# STM32F429ZI.net
KiCad netlist of a schematic drawn in Altium Designer
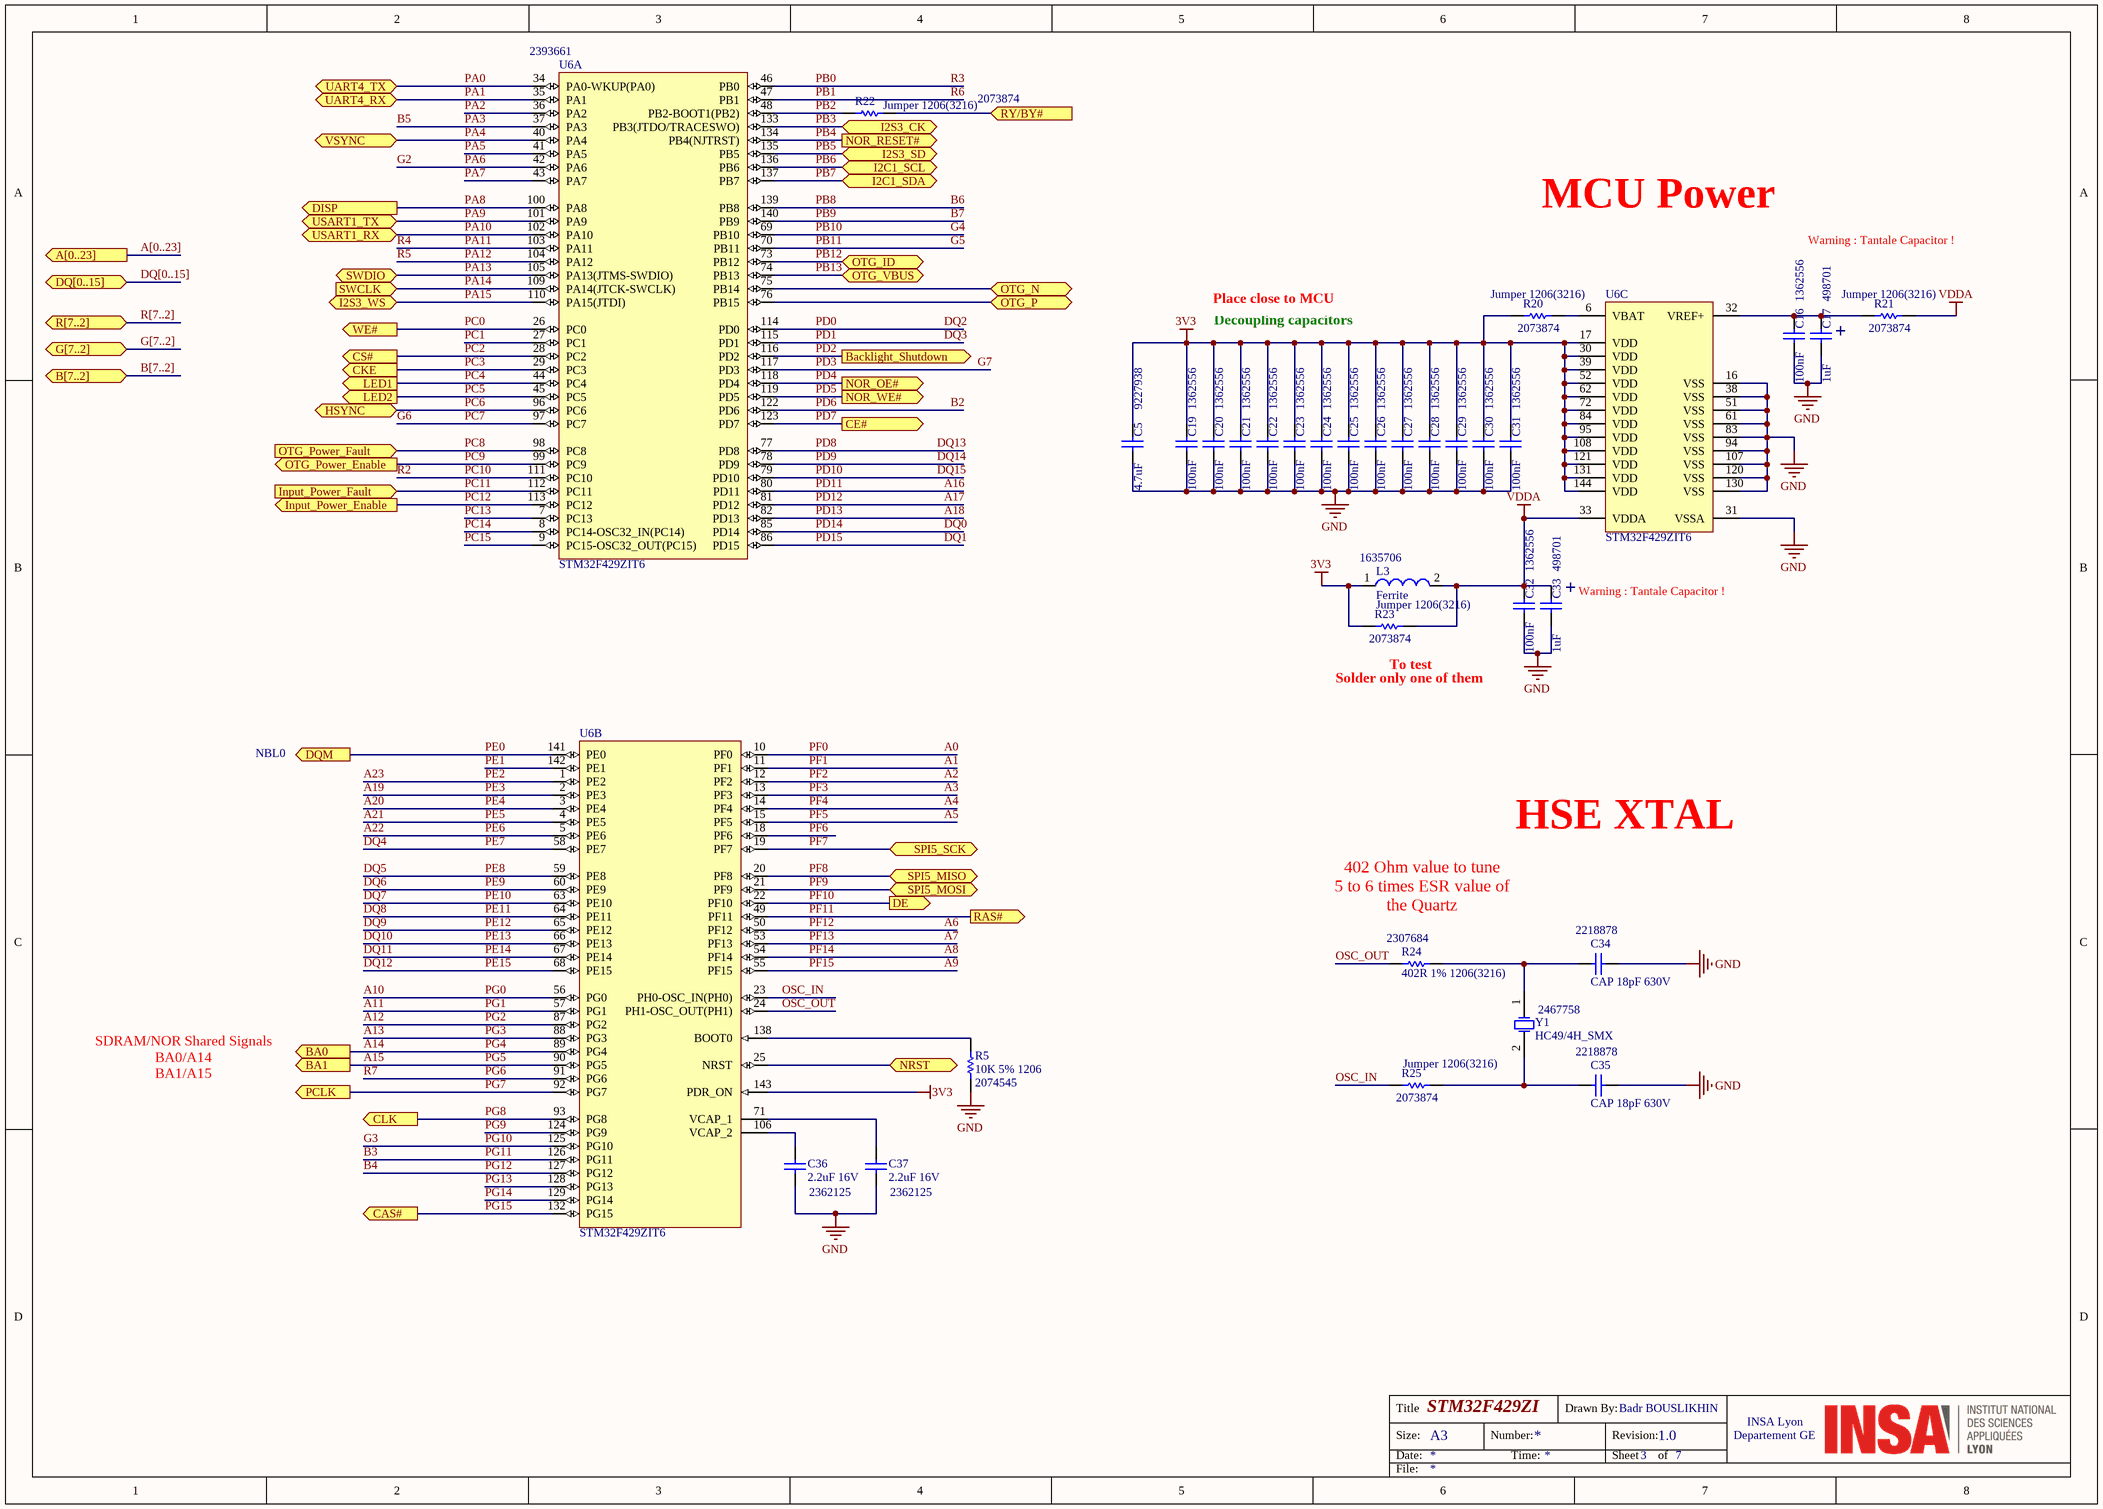
[diagram p0: STM32F429ZI.SchDoc]

(export (version "E")
  (design (tool "Eeschema 10.0.6"))
  (components
    (comp (ref "C5")
      (value "4.7uF")
      (footprint "CAPC1206(3216)190_N")
      (description "CAP 4.7uF 50V ±10% 1206 (3216 Metric) Thickness 1.9mm SMD")
      (fields (field (name "TOLERANCE") "±10%") (field (name "SUPPLIER PART NUMBER 1") "9227938"))
      (libsource (lib "Altium Content Vault") (part "CAP"))
    )
    (comp (ref "C16")
      (value "100nF")
      (footprint "CAPC0603(1608)100_N")
      (description "CAP 100nF 50V ±10% 0603 (1608 Metric) Thickness 1mm SMD")
      (fields (field (name "TOLERANCE") "±10%") (field (name "SUPPLIER PART NUMBER 1") "1362556"))
      (libsource (lib "Altium Content Vault") (part "CMP-1035-02592-1"))
    )
    (comp (ref "C17")
      (value "1uF")
      (footprint "CAPC1206(3216)170_L")
      (description "CAP 1uF 16V ±10% 1206 (3216 Metric) Thickness 1.7mm SMD")
      (fields (field (name "TOLERANCE") "±10%") (field (name "SUPPLIER PART NUMBER 1") "498701"))
      (libsource (lib "Altium Content Vault") (part "CAP"))
    )
    (comp (ref "C19")
      (value "100nF")
      (footprint "CAPC0603(1608)100_N")
      (description "CAP 100nF 50V ±10% 0603 (1608 Metric) Thickness 1mm SMD")
      (fields (field (name "TOLERANCE") "±10%") (field (name "SUPPLIER PART NUMBER 1") "1362556"))
      (libsource (lib "Altium Content Vault") (part "CMP-1035-02592-1"))
    )
    (comp (ref "C20")
      (value "100nF")
      (footprint "CAPC0603(1608)100_N")
      (description "CAP 100nF 50V ±10% 0603 (1608 Metric) Thickness 1mm SMD")
      (fields (field (name "TOLERANCE") "±10%") (field (name "SUPPLIER PART NUMBER 1") "1362556"))
      (libsource (lib "Altium Content Vault") (part "CMP-1035-02592-1"))
    )
    (comp (ref "C21")
      (value "100nF")
      (footprint "CAPC0603(1608)100_N")
      (description "CAP 100nF 50V ±10% 0603 (1608 Metric) Thickness 1mm SMD")
      (fields (field (name "TOLERANCE") "±10%") (field (name "SUPPLIER PART NUMBER 1") "1362556"))
      (libsource (lib "Altium Content Vault") (part "CMP-1035-02592-1"))
    )
    (comp (ref "C22")
      (value "100nF")
      (footprint "CAPC0603(1608)100_N")
      (description "CAP 100nF 50V ±10% 0603 (1608 Metric) Thickness 1mm SMD")
      (fields (field (name "TOLERANCE") "±10%") (field (name "SUPPLIER PART NUMBER 1") "1362556"))
      (libsource (lib "Altium Content Vault") (part "CMP-1035-02592-1"))
    )
    (comp (ref "C23")
      (value "100nF")
      (footprint "CAPC0603(1608)100_N")
      (description "CAP 100nF 50V ±10% 0603 (1608 Metric) Thickness 1mm SMD")
      (fields (field (name "TOLERANCE") "±10%") (field (name "SUPPLIER PART NUMBER 1") "1362556"))
      (libsource (lib "Altium Content Vault") (part "CMP-1035-02592-1"))
    )
    (comp (ref "C24")
      (value "100nF")
      (footprint "CAPC0603(1608)100_N")
      (description "CAP 100nF 50V ±10% 0603 (1608 Metric) Thickness 1mm SMD")
      (fields (field (name "TOLERANCE") "±10%") (field (name "SUPPLIER PART NUMBER 1") "1362556"))
      (libsource (lib "Altium Content Vault") (part "CMP-1035-02592-1"))
    )
    (comp (ref "C25")
      (value "100nF")
      (footprint "CAPC0603(1608)100_N")
      (description "CAP 100nF 50V ±10% 0603 (1608 Metric) Thickness 1mm SMD")
      (fields (field (name "TOLERANCE") "±10%") (field (name "SUPPLIER PART NUMBER 1") "1362556"))
      (libsource (lib "Altium Content Vault") (part "CMP-1035-02592-1"))
    )
    (comp (ref "C26")
      (value "100nF")
      (footprint "CAPC0603(1608)100_N")
      (description "CAP 100nF 50V ±10% 0603 (1608 Metric) Thickness 1mm SMD")
      (fields (field (name "TOLERANCE") "±10%") (field (name "SUPPLIER PART NUMBER 1") "1362556"))
      (libsource (lib "Altium Content Vault") (part "CMP-1035-02592-1"))
    )
    (comp (ref "C27")
      (value "100nF")
      (footprint "CAPC0603(1608)100_N")
      (description "CAP 100nF 50V ±10% 0603 (1608 Metric) Thickness 1mm SMD")
      (fields (field (name "TOLERANCE") "±10%") (field (name "SUPPLIER PART NUMBER 1") "1362556"))
      (libsource (lib "Altium Content Vault") (part "CMP-1035-02592-1"))
    )
    (comp (ref "C28")
      (value "100nF")
      (footprint "CAPC0603(1608)100_N")
      (description "CAP 100nF 50V ±10% 0603 (1608 Metric) Thickness 1mm SMD")
      (fields (field (name "TOLERANCE") "±10%") (field (name "SUPPLIER PART NUMBER 1") "1362556"))
      (libsource (lib "Altium Content Vault") (part "CMP-1035-02592-1"))
    )
    (comp (ref "C29")
      (value "100nF")
      (footprint "CAPC0603(1608)100_N")
      (description "CAP 100nF 50V ±10% 0603 (1608 Metric) Thickness 1mm SMD")
      (fields (field (name "TOLERANCE") "±10%") (field (name "SUPPLIER PART NUMBER 1") "1362556"))
      (libsource (lib "Altium Content Vault") (part "CMP-1035-02592-1"))
    )
    (comp (ref "C30")
      (value "100nF")
      (footprint "CAPC0603(1608)100_N")
      (description "CAP 100nF 50V ±10% 0603 (1608 Metric) Thickness 1mm SMD")
      (fields (field (name "TOLERANCE") "±10%") (field (name "SUPPLIER PART NUMBER 1") "1362556"))
      (libsource (lib "Altium Content Vault") (part "CMP-1035-02592-1"))
    )
    (comp (ref "C31")
      (value "100nF")
      (footprint "CAPC0603(1608)100_N")
      (description "CAP 100nF 50V ±10% 0603 (1608 Metric) Thickness 1mm SMD")
      (fields (field (name "TOLERANCE") "±10%") (field (name "SUPPLIER PART NUMBER 1") "1362556"))
      (libsource (lib "Altium Content Vault") (part "CMP-1035-02592-1"))
    )
    (comp (ref "C32")
      (value "100nF")
      (footprint "CAPC0603(1608)100_N")
      (description "CAP 100nF 50V ±10% 0603 (1608 Metric) Thickness 1mm SMD")
      (fields (field (name "TOLERANCE") "±10%") (field (name "SUPPLIER PART NUMBER 1") "1362556"))
      (libsource (lib "Altium Content Vault") (part "CMP-1035-02592-1"))
    )
    (comp (ref "C33")
      (value "1uF")
      (footprint "CAPC1206(3216)170_L")
      (description "CAP 1uF 16V ±10% 1206 (3216 Metric) Thickness 1.7mm SMD")
      (fields (field (name "TOLERANCE") "±10%") (field (name "SUPPLIER PART NUMBER 1") "498701"))
      (libsource (lib "Altium Content Vault") (part "CAP"))
    )
    (comp (ref "C34")
      (value "CAP 18pF 630V")
      (footprint "CAPC1206(3216)170_L")
      (description "CAP 18pF 500V ±5% 1206 (3216 Metric) Thickness 1.7mm SMD")
      (fields (field (name "TOLERANCE") "±5%") (field (name "SUPPLIER PART NUMBER 1") "2218878"))
      (libsource (lib "Altium Content Vault") (part "CMP-1037-00919-1"))
    )
    (comp (ref "C35")
      (value "CAP 18pF 630V")
      (footprint "CAPC1206(3216)170_L")
      (description "CAP 18pF 500V ±5% 1206 (3216 Metric) Thickness 1.7mm SMD")
      (fields (field (name "TOLERANCE") "±5%") (field (name "SUPPLIER PART NUMBER 1") "2218878"))
      (libsource (lib "Altium Content Vault") (part "CMP-1037-00919-1"))
    )
    (comp (ref "C36")
      (value "2.2uF 16V")
      (footprint "CAPC1206(3216)190_L")
      (description "CAP 2.2uF 16V ±20% 1206 (3216 Metric) Thickness 1.9mm SMD")
      (fields (field (name "TOLERANCE") "±20%") (field (name "SUPPLIER PART NUMBER 1") "2362125"))
      (libsource (lib "Altium Content Vault") (part "CMP-1037-04816-1"))
    )
    (comp (ref "C37")
      (value "2.2uF 16V")
      (footprint "CAPC1206(3216)190_L")
      (description "CAP 2.2uF 16V ±20% 1206 (3216 Metric) Thickness 1.9mm SMD")
      (fields (field (name "TOLERANCE") "±20%") (field (name "SUPPLIER PART NUMBER 1") "2362125"))
      (libsource (lib "Altium Content Vault") (part "CMP-1037-04816-1"))
    )
    (comp (ref "L3")
      (value "Ferrite")
      (footprint "SMD-0603")
      (description "SMD EMI Suppression Ferrite Bead WE-CBF, Z = 600 Ohm")
      (fields (field (name "SUPPLIER PART NUMBER 1") "1635706"))
      (libsource (lib "Altium Content Vault") (part "CMP-0220-00181-1"))
    )
    (comp (ref "R5")
      (value "10K 5% 1206")
      (footprint "RESC1206(3216)_M")
      (description "10K 0.25W 5% 1206 (3216 Metric)  SMD")
      (fields
        (field (name "POWER") "0.25 W")
        (field (name "TOLERANCE") "5 %")
        (field (name "SUPPLIER PART NUMBER 1") "2074545")
      )
      (libsource (lib "Altium Content Vault") (part "CMP-1014-00098-1"))
    )
    (comp (ref "R20")
      (value "Jumper 1206(3216)")
      (footprint "RESC1206(3216)_L")
      (description "Jumper 1206 (3216 Metric)")
      (fields (field (name "TOLERANCE") "None") (field (name "SUPPLIER PART NUMBER 1") "2073874"))
      (libsource (lib "Altium Content Vault") (part "RES"))
    )
    (comp (ref "R21")
      (value "Jumper 1206(3216)")
      (footprint "RESC1206(3216)_L")
      (description "Jumper 1206 (3216 Metric)")
      (fields (field (name "TOLERANCE") "None") (field (name "SUPPLIER PART NUMBER 1") "2073874"))
      (libsource (lib "Altium Content Vault") (part "RES"))
    )
    (comp (ref "R22")
      (value "Jumper 1206(3216)")
      (footprint "RESC1206(3216)_L")
      (description "Jumper 1206 (3216 Metric)")
      (fields (field (name "TOLERANCE") "None") (field (name "SUPPLIER PART NUMBER 1") "2073874"))
      (libsource (lib "Altium Content Vault") (part "RES"))
    )
    (comp (ref "R23")
      (value "Jumper 1206(3216)")
      (footprint "RESC1206(3216)_L")
      (description "Jumper 1206 (3216 Metric)")
      (fields (field (name "TOLERANCE") "None") (field (name "SUPPLIER PART NUMBER 1") "2073874"))
      (libsource (lib "Altium Content Vault") (part "RES"))
    )
    (comp (ref "R24")
      (value "402R 1% 1206(3216)")
      (footprint "RESC1206(3216)_L")
      (description "402R 0.25W 1% 1206 (3216 Metric)  SMD")
      (fields
        (field (name "POWER") "0.25 W")
        (field (name "TOLERANCE") "1 %")
        (field (name "SUPPLIER PART NUMBER 1") "2307684")
      )
      (libsource (lib "Altium Content Vault") (part "RES"))
    )
    (comp (ref "R25")
      (value "Jumper 1206(3216)")
      (footprint "RESC1206(3216)_L")
      (description "Jumper 1206 (3216 Metric)")
      (fields (field (name "TOLERANCE") "None") (field (name "SUPPLIER PART NUMBER 1") "2073874"))
      (libsource (lib "Altium Content Vault") (part "RES"))
    )
    (comp (ref "U6")
      (value "STM32F429ZIT6")
      (footprint "STM-LQFP144_L")
      (fields
        (field (name "MANUFACTURER") "STMicroelectronics")
        (field (name "SUPPLIER PART NUMBER 1") "2393661")
      )
      (libsource (lib "Altium Content Vault") (part "MC-ARM-STM32F4X9-SQ144"))
    )
    (comp (ref "Y1")
      (value "HC49/4H_SMX")
      (footprint "HC49/4H_SMX")
      (description "Surface Mount Quartz Crystal")
      (fields (field (name "SUPPLIER PART NUMBER 1") "2467758") (field (name "PUBLISHER") "Altium Limited"))
      (libsource (lib "C-MAC Crystal Oscillator") (part "HC49/4H_SMX"))
    )
  )
  (nets
    (net (code "1") (name "/A0") (class "Default")
      (node (ref "U6") (pin "10") (pinfunction "PF0_10") (pintype "bidirectional"))
    )
    (net (code "2") (name "/A1") (class "Default")
      (node (ref "U6") (pin "11") (pinfunction "PF1_11") (pintype "bidirectional"))
    )
    (net (code "3") (name "/A2") (class "Default")
      (node (ref "U6") (pin "12") (pinfunction "PF2_12") (pintype "bidirectional"))
    )
    (net (code "4") (name "/A3") (class "Default")
      (node (ref "U6") (pin "13") (pinfunction "PF3_13") (pintype "bidirectional"))
    )
    (net (code "5") (name "/A4") (class "Default")
      (node (ref "U6") (pin "14") (pinfunction "PF4_14") (pintype "bidirectional"))
    )
    (net (code "6") (name "/A5") (class "Default")
      (node (ref "U6") (pin "15") (pinfunction "PF5_15") (pintype "bidirectional"))
    )
    (net (code "7") (name "/A6") (class "Default")
      (node (ref "U6") (pin "50") (pinfunction "PF12_50") (pintype "bidirectional"))
    )
    (net (code "8") (name "/A7") (class "Default")
      (node (ref "U6") (pin "53") (pinfunction "PF13_53") (pintype "bidirectional"))
    )
    (net (code "9") (name "/A8") (class "Default")
      (node (ref "U6") (pin "54") (pinfunction "PF14_54") (pintype "bidirectional"))
    )
    (net (code "10") (name "/A9") (class "Default")
      (node (ref "U6") (pin "55") (pinfunction "PF15_55") (pintype "bidirectional"))
    )
    (net (code "11") (name "/A10") (class "Default")
      (node (ref "U6") (pin "56") (pinfunction "PG0_56") (pintype "bidirectional"))
    )
    (net (code "12") (name "/A11") (class "Default")
      (node (ref "U6") (pin "57") (pinfunction "PG1_57") (pintype "bidirectional"))
    )
    (net (code "13") (name "/A12") (class "Default")
      (node (ref "U6") (pin "87") (pinfunction "PG2_87") (pintype "bidirectional"))
    )
    (net (code "14") (name "/A13") (class "Default")
      (node (ref "U6") (pin "88") (pinfunction "PG3_88") (pintype "bidirectional"))
    )
    (net (code "15") (name "/A14") (class "Default")
      (node (ref "U6") (pin "89") (pinfunction "PG4_89") (pintype "bidirectional"))
    )
    (net (code "16") (name "/A15") (class "Default")
      (node (ref "U6") (pin "90") (pinfunction "PG5_90") (pintype "bidirectional"))
    )
    (net (code "17") (name "/A16") (class "Default")
      (node (ref "U6") (pin "80") (pinfunction "PD11_80") (pintype "bidirectional"))
    )
    (net (code "18") (name "/A17") (class "Default")
      (node (ref "U6") (pin "81") (pinfunction "PD12_81") (pintype "bidirectional"))
    )
    (net (code "19") (name "/A18") (class "Default")
      (node (ref "U6") (pin "82") (pinfunction "PD13_82") (pintype "bidirectional"))
    )
    (net (code "20") (name "/A19") (class "Default")
      (node (ref "U6") (pin "2") (pinfunction "PE3_2") (pintype "bidirectional"))
    )
    (net (code "21") (name "/A20") (class "Default")
      (node (ref "U6") (pin "3") (pinfunction "PE4_3") (pintype "bidirectional"))
    )
    (net (code "22") (name "/A21") (class "Default")
      (node (ref "U6") (pin "4") (pinfunction "PE5_4") (pintype "bidirectional"))
    )
    (net (code "23") (name "/A22") (class "Default")
      (node (ref "U6") (pin "5") (pinfunction "PE6_5") (pintype "bidirectional"))
    )
    (net (code "24") (name "/A23") (class "Default")
      (node (ref "U6") (pin "1") (pinfunction "PE2_1") (pintype "bidirectional"))
    )
    (net (code "26") (name "/B2") (class "Default")
      (node (ref "U6") (pin "122") (pinfunction "PD6_122") (pintype "bidirectional"))
    )
    (net (code "27") (name "/B3") (class "Default")
      (node (ref "U6") (pin "126") (pinfunction "PG11_126") (pintype "bidirectional"))
    )
    (net (code "28") (name "/B4") (class "Default")
      (node (ref "U6") (pin "127") (pinfunction "PG12_127") (pintype "bidirectional"))
    )
    (net (code "29") (name "/B5") (class "Default")
      (node (ref "U6") (pin "37") (pinfunction "PA3_37") (pintype "bidirectional"))
    )
    (net (code "30") (name "/B6") (class "Default")
      (node (ref "U6") (pin "139") (pinfunction "PB8_139") (pintype "bidirectional"))
    )
    (net (code "31") (name "/B7") (class "Default")
      (node (ref "U6") (pin "140") (pinfunction "PB9_140") (pintype "bidirectional"))
    )
    (net (code "33") (name "/DQ0") (class "Default")
      (node (ref "U6") (pin "85") (pinfunction "PD14_85") (pintype "bidirectional"))
    )
    (net (code "34") (name "/DQ1") (class "Default")
      (node (ref "U6") (pin "86") (pinfunction "PD15_86") (pintype "bidirectional"))
    )
    (net (code "35") (name "/DQ2") (class "Default")
      (node (ref "U6") (pin "114") (pinfunction "PD0_114") (pintype "bidirectional"))
    )
    (net (code "36") (name "/DQ3") (class "Default")
      (node (ref "U6") (pin "115") (pinfunction "PD1_115") (pintype "bidirectional"))
    )
    (net (code "37") (name "/DQ4") (class "Default")
      (node (ref "U6") (pin "58") (pinfunction "PE7_58") (pintype "bidirectional"))
    )
    (net (code "38") (name "/DQ5") (class "Default")
      (node (ref "U6") (pin "59") (pinfunction "PE8_59") (pintype "bidirectional"))
    )
    (net (code "39") (name "/DQ6") (class "Default")
      (node (ref "U6") (pin "60") (pinfunction "PE9_60") (pintype "bidirectional"))
    )
    (net (code "40") (name "/DQ7") (class "Default")
      (node (ref "U6") (pin "63") (pinfunction "PE10_63") (pintype "bidirectional"))
    )
    (net (code "41") (name "/DQ8") (class "Default")
      (node (ref "U6") (pin "64") (pinfunction "PE11_64") (pintype "bidirectional"))
    )
    (net (code "42") (name "/DQ9") (class "Default")
      (node (ref "U6") (pin "65") (pinfunction "PE12_65") (pintype "bidirectional"))
    )
    (net (code "43") (name "/DQ10") (class "Default")
      (node (ref "U6") (pin "66") (pinfunction "PE13_66") (pintype "bidirectional"))
    )
    (net (code "44") (name "/DQ11") (class "Default")
      (node (ref "U6") (pin "67") (pinfunction "PE14_67") (pintype "bidirectional"))
    )
    (net (code "45") (name "/DQ12") (class "Default")
      (node (ref "U6") (pin "68") (pinfunction "PE15_68") (pintype "bidirectional"))
    )
    (net (code "46") (name "/DQ13") (class "Default")
      (node (ref "U6") (pin "77") (pinfunction "PD8_77") (pintype "bidirectional"))
    )
    (net (code "47") (name "/DQ14") (class "Default")
      (node (ref "U6") (pin "78") (pinfunction "PD9_78") (pintype "bidirectional"))
    )
    (net (code "48") (name "/DQ15") (class "Default")
      (node (ref "U6") (pin "79") (pinfunction "PD10_79") (pintype "bidirectional"))
    )
    (net (code "50") (name "/G2") (class "Default")
      (node (ref "U6") (pin "42") (pinfunction "PA6_42") (pintype "bidirectional"))
    )
    (net (code "51") (name "/G3") (class "Default")
      (node (ref "U6") (pin "125") (pinfunction "PG10_125") (pintype "bidirectional"))
    )
    (net (code "52") (name "/G4") (class "Default")
      (node (ref "U6") (pin "69") (pinfunction "PB10_69") (pintype "bidirectional"))
    )
    (net (code "53") (name "/G5") (class "Default")
      (node (ref "U6") (pin "70") (pinfunction "PB11_70") (pintype "bidirectional"))
    )
    (net (code "54") (name "/G6") (class "Default")
      (node (ref "U6") (pin "97") (pinfunction "PC7_97") (pintype "bidirectional"))
    )
    (net (code "55") (name "/G7") (class "Default")
      (node (ref "U6") (pin "117") (pinfunction "PD3_117") (pintype "bidirectional"))
    )
    (net (code "57") (name "/NRST") (class "Default")
      (node (ref "U6") (pin "25") (pinfunction "NRST_25") (pintype "bidirectional"))
    )
    (net (code "58") (name "/OSC_IN") (class "Default")
      (node (ref "R25") (pin "1") (pinfunction "1_1") (pintype "passive"))
      (node (ref "U6") (pin "23") (pinfunction "PH0-OSC_IN(PH0)_23") (pintype "bidirectional"))
    )
    (net (code "59") (name "/OSC_OUT") (class "Default")
      (node (ref "R24") (pin "1") (pinfunction "1_1") (pintype "passive"))
      (node (ref "U6") (pin "24") (pinfunction "PH1-OSC_OUT(PH1)_24") (pintype "bidirectional"))
    )
    (net (code "60") (name "/OTG_N") (class "Default")
      (node (ref "U6") (pin "75") (pinfunction "PB14_75") (pintype "bidirectional"))
    )
    (net (code "61") (name "/OTG_P") (class "Default")
      (node (ref "U6") (pin "76") (pinfunction "PB15_76") (pintype "bidirectional"))
    )
    (net (code "62") (name "/PA0") (class "Default")
      (node (ref "U6") (pin "34") (pinfunction "PA0-WKUP(PA0)_34") (pintype "bidirectional"))
    )
    (net (code "63") (name "/PA1") (class "Default")
      (node (ref "U6") (pin "35") (pinfunction "PA1_35") (pintype "bidirectional"))
    )
    (net (code "64") (name "/PA2") (class "Default")
      (node (ref "U6") (pin "36") (pinfunction "PA2_36") (pintype "bidirectional"))
    )
    (net (code "65") (name "/PA4") (class "Default")
      (node (ref "U6") (pin "40") (pinfunction "PA4_40") (pintype "bidirectional"))
    )
    (net (code "66") (name "/PA5") (class "Default")
      (node (ref "U6") (pin "41") (pinfunction "PA5_41") (pintype "bidirectional"))
    )
    (net (code "67") (name "/PA7") (class "Default")
      (node (ref "U6") (pin "43") (pinfunction "PA7_43") (pintype "bidirectional"))
    )
    (net (code "68") (name "/PA8") (class "Default")
      (node (ref "U6") (pin "100") (pinfunction "PA8_100") (pintype "bidirectional"))
    )
    (net (code "69") (name "/PA9") (class "Default")
      (node (ref "U6") (pin "101") (pinfunction "PA9_101") (pintype "bidirectional"))
    )
    (net (code "70") (name "/PA10") (class "Default")
      (node (ref "U6") (pin "102") (pinfunction "PA10_102") (pintype "bidirectional"))
    )
    (net (code "71") (name "/PA13") (class "Default")
      (node (ref "U6") (pin "105") (pinfunction "PA13(JTMS-SWDIO)_105") (pintype "bidirectional"))
    )
    (net (code "72") (name "/PA14") (class "Default")
      (node (ref "U6") (pin "109") (pinfunction "PA14(JTCK-SWCLK)_109") (pintype "bidirectional"))
    )
    (net (code "73") (name "/PA15") (class "Default")
      (node (ref "U6") (pin "110") (pinfunction "PA15(JTDI)_110") (pintype "bidirectional"))
    )
    (net (code "74") (name "/PB2") (class "Default")
      (node (ref "R22") (pin "1") (pinfunction "1_1") (pintype "passive"))
      (node (ref "U6") (pin "48") (pinfunction "PB2-BOOT1(PB2)_48") (pintype "bidirectional"))
    )
    (net (code "75") (name "/PB3") (class "Default")
      (node (ref "U6") (pin "133") (pinfunction "PB3(JTDO/TRACESWO)_133") (pintype "bidirectional"))
    )
    (net (code "76") (name "/PB4") (class "Default")
      (node (ref "U6") (pin "134") (pinfunction "PB4(NJTRST)_134") (pintype "bidirectional"))
    )
    (net (code "77") (name "/PB5") (class "Default")
      (node (ref "U6") (pin "135") (pinfunction "PB5_135") (pintype "bidirectional"))
    )
    (net (code "78") (name "/PB6") (class "Default")
      (node (ref "U6") (pin "136") (pinfunction "PB6_136") (pintype "bidirectional"))
    )
    (net (code "79") (name "/PB7") (class "Default")
      (node (ref "U6") (pin "137") (pinfunction "PB7_137") (pintype "bidirectional"))
    )
    (net (code "80") (name "/PB12") (class "Default")
      (node (ref "U6") (pin "73") (pinfunction "PB12_73") (pintype "bidirectional"))
    )
    (net (code "81") (name "/PB13") (class "Default")
      (node (ref "U6") (pin "74") (pinfunction "PB13_74") (pintype "bidirectional"))
    )
    (net (code "82") (name "/PC0") (class "Default")
      (node (ref "U6") (pin "26") (pinfunction "PC0_26") (pintype "bidirectional"))
    )
    (net (code "83") (name "/PC1") (class "Default")
      (node (ref "U6") (pin "27") (pinfunction "PC1_27") (pintype "bidirectional"))
    )
    (net (code "84") (name "/PC2") (class "Default")
      (node (ref "U6") (pin "28") (pinfunction "PC2_28") (pintype "bidirectional"))
    )
    (net (code "85") (name "/PC3") (class "Default")
      (node (ref "U6") (pin "29") (pinfunction "PC3_29") (pintype "bidirectional"))
    )
    (net (code "86") (name "/PC4") (class "Default")
      (node (ref "U6") (pin "44") (pinfunction "PC4_44") (pintype "bidirectional"))
    )
    (net (code "87") (name "/PC5") (class "Default")
      (node (ref "U6") (pin "45") (pinfunction "PC5_45") (pintype "bidirectional"))
    )
    (net (code "88") (name "/PC6") (class "Default")
      (node (ref "U6") (pin "96") (pinfunction "PC6_96") (pintype "bidirectional"))
    )
    (net (code "89") (name "/PC8") (class "Default")
      (node (ref "U6") (pin "98") (pinfunction "PC8_98") (pintype "bidirectional"))
    )
    (net (code "90") (name "/PC9") (class "Default")
      (node (ref "U6") (pin "99") (pinfunction "PC9_99") (pintype "bidirectional"))
    )
    (net (code "91") (name "/PC11") (class "Default")
      (node (ref "U6") (pin "112") (pinfunction "PC11_112") (pintype "bidirectional"))
    )
    (net (code "92") (name "/PC12") (class "Default")
      (node (ref "U6") (pin "113") (pinfunction "PC12_113") (pintype "bidirectional"))
    )
    (net (code "93") (name "/PC13") (class "Default")
      (node (ref "U6") (pin "7") (pinfunction "PC13_7") (pintype "bidirectional"))
    )
    (net (code "94") (name "/PC14") (class "Default")
      (node (ref "U6") (pin "8") (pinfunction "PC14-OSC32_IN(PC14)_8") (pintype "bidirectional"))
    )
    (net (code "95") (name "/PC15") (class "Default")
      (node (ref "U6") (pin "9") (pinfunction "PC15-OSC32_OUT(PC15)_9") (pintype "bidirectional"))
    )
    (net (code "96") (name "/PD2") (class "Default")
      (node (ref "U6") (pin "116") (pinfunction "PD2_116") (pintype "bidirectional"))
    )
    (net (code "97") (name "/PD4") (class "Default")
      (node (ref "U6") (pin "118") (pinfunction "PD4_118") (pintype "bidirectional"))
    )
    (net (code "98") (name "/PD5") (class "Default")
      (node (ref "U6") (pin "119") (pinfunction "PD5_119") (pintype "bidirectional"))
    )
    (net (code "99") (name "/PD7") (class "Default")
      (node (ref "U6") (pin "123") (pinfunction "PD7_123") (pintype "bidirectional"))
    )
    (net (code "100") (name "/PE0") (class "Default")
      (node (ref "U6") (pin "141") (pinfunction "PE0_141") (pintype "bidirectional"))
    )
    (net (code "101") (name "/PE1") (class "Default")
      (node (ref "U6") (pin "142") (pinfunction "PE1_142") (pintype "bidirectional"))
    )
    (net (code "102") (name "/PF6") (class "Default")
      (node (ref "U6") (pin "18") (pinfunction "PF6_18") (pintype "bidirectional"))
    )
    (net (code "103") (name "/PF7") (class "Default")
      (node (ref "U6") (pin "19") (pinfunction "PF7_19") (pintype "bidirectional"))
    )
    (net (code "104") (name "/PF8") (class "Default")
      (node (ref "U6") (pin "20") (pinfunction "PF8_20") (pintype "bidirectional"))
    )
    (net (code "105") (name "/PF9") (class "Default")
      (node (ref "U6") (pin "21") (pinfunction "PF9_21") (pintype "bidirectional"))
    )
    (net (code "106") (name "/PF10") (class "Default")
      (node (ref "U6") (pin "22") (pinfunction "PF10_22") (pintype "bidirectional"))
    )
    (net (code "107") (name "/PF11") (class "Default")
      (node (ref "U6") (pin "49") (pinfunction "PF11_49") (pintype "bidirectional"))
    )
    (net (code "108") (name "/PG7") (class "Default")
      (node (ref "U6") (pin "92") (pinfunction "PG7_92") (pintype "bidirectional"))
    )
    (net (code "109") (name "/PG8") (class "Default")
      (node (ref "U6") (pin "93") (pinfunction "PG8_93") (pintype "bidirectional"))
    )
    (net (code "110") (name "/PG9") (class "Default")
      (node (ref "U6") (pin "124") (pinfunction "PG9_124") (pintype "bidirectional"))
    )
    (net (code "111") (name "/PG13") (class "Default")
      (node (ref "U6") (pin "128") (pinfunction "PG13_128") (pintype "bidirectional"))
    )
    (net (code "112") (name "/PG14") (class "Default")
      (node (ref "U6") (pin "129") (pinfunction "PG14_129") (pintype "bidirectional"))
    )
    (net (code "113") (name "/PG15") (class "Default")
      (node (ref "U6") (pin "132") (pinfunction "PG15_132") (pintype "bidirectional"))
    )
    (net (code "114") (name "/R2") (class "Default")
      (node (ref "U6") (pin "111") (pinfunction "PC10_111") (pintype "bidirectional"))
    )
    (net (code "115") (name "/R3") (class "Default")
      (node (ref "U6") (pin "46") (pinfunction "PB0_46") (pintype "bidirectional"))
    )
    (net (code "116") (name "/R4") (class "Default")
      (node (ref "U6") (pin "103") (pinfunction "PA11_103") (pintype "bidirectional"))
    )
    (net (code "117") (name "/R5") (class "Default")
      (node (ref "U6") (pin "104") (pinfunction "PA12_104") (pintype "bidirectional"))
    )
    (net (code "118") (name "/R6") (class "Default")
      (node (ref "U6") (pin "47") (pinfunction "PB1_47") (pintype "bidirectional"))
    )
    (net (code "119") (name "/R7") (class "Default")
      (node (ref "U6") (pin "91") (pinfunction "PG6_91") (pintype "bidirectional"))
    )
    (net (code "120") (name "/RY{slash}BY#") (class "Default")
      (node (ref "R22") (pin "2") (pinfunction "2_2") (pintype "passive"))
    )
    (net (code "122") (name "3V3") (class "Default")
      (node (ref "C19") (pin "2") (pinfunction "2_2") (pintype "passive"))
      (node (ref "C20") (pin "2") (pinfunction "2_2") (pintype "passive"))
      (node (ref "C21") (pin "2") (pinfunction "2_2") (pintype "passive"))
      (node (ref "C22") (pin "2") (pinfunction "2_2") (pintype "passive"))
      (node (ref "C23") (pin "2") (pinfunction "2_2") (pintype "passive"))
      (node (ref "C24") (pin "2") (pinfunction "2_2") (pintype "passive"))
      (node (ref "C25") (pin "2") (pinfunction "2_2") (pintype "passive"))
      (node (ref "C26") (pin "2") (pinfunction "2_2") (pintype "passive"))
      (node (ref "C27") (pin "2") (pinfunction "2_2") (pintype "passive"))
      (node (ref "C28") (pin "2") (pinfunction "2_2") (pintype "passive"))
      (node (ref "C29") (pin "2") (pinfunction "2_2") (pintype "passive"))
      (node (ref "C30") (pin "2") (pinfunction "2_2") (pintype "passive"))
      (node (ref "C31") (pin "2") (pinfunction "2_2") (pintype "passive"))
      (node (ref "C5") (pin "2") (pinfunction "2_2") (pintype "passive"))
      (node (ref "L3") (pin "1") (pinfunction "1_1") (pintype "passive"))
      (node (ref "R20") (pin "1") (pinfunction "1_1") (pintype "passive"))
      (node (ref "R23") (pin "1") (pinfunction "1_1") (pintype "passive"))
      (node (ref "U6") (pin "108") (pinfunction "VDD_108") (pintype "power_in"))
      (node (ref "U6") (pin "121") (pinfunction "VDD_121") (pintype "power_in"))
      (node (ref "U6") (pin "131") (pinfunction "VDD_131") (pintype "power_in"))
      (node (ref "U6") (pin "143") (pinfunction "PDR_ON_143") (pintype "input"))
      (node (ref "U6") (pin "144") (pinfunction "VDD_144") (pintype "power_in"))
      (node (ref "U6") (pin "17") (pinfunction "VDD_17") (pintype "power_in"))
      (node (ref "U6") (pin "30") (pinfunction "VDD_30") (pintype "power_in"))
      (node (ref "U6") (pin "39") (pinfunction "VDD_39") (pintype "power_in"))
      (node (ref "U6") (pin "52") (pinfunction "VDD_52") (pintype "power_in"))
      (node (ref "U6") (pin "62") (pinfunction "VDD_62") (pintype "power_in"))
      (node (ref "U6") (pin "72") (pinfunction "VDD_72") (pintype "power_in"))
      (node (ref "U6") (pin "84") (pinfunction "VDD_84") (pintype "power_in"))
      (node (ref "U6") (pin "95") (pinfunction "VDD_95") (pintype "power_in"))
    )
    (net (code "123") (name "GND") (class "Default")
      (node (ref "C16") (pin "1") (pinfunction "1_1") (pintype "passive"))
      (node (ref "C17") (pin "1") (pinfunction "1_1") (pintype "passive"))
      (node (ref "C19") (pin "1") (pinfunction "1_1") (pintype "passive"))
      (node (ref "C20") (pin "1") (pinfunction "1_1") (pintype "passive"))
      (node (ref "C21") (pin "1") (pinfunction "1_1") (pintype "passive"))
      (node (ref "C22") (pin "1") (pinfunction "1_1") (pintype "passive"))
      (node (ref "C23") (pin "1") (pinfunction "1_1") (pintype "passive"))
      (node (ref "C24") (pin "1") (pinfunction "1_1") (pintype "passive"))
      (node (ref "C25") (pin "1") (pinfunction "1_1") (pintype "passive"))
      (node (ref "C26") (pin "1") (pinfunction "1_1") (pintype "passive"))
      (node (ref "C27") (pin "1") (pinfunction "1_1") (pintype "passive"))
      (node (ref "C28") (pin "1") (pinfunction "1_1") (pintype "passive"))
      (node (ref "C29") (pin "1") (pinfunction "1_1") (pintype "passive"))
      (node (ref "C30") (pin "1") (pinfunction "1_1") (pintype "passive"))
      (node (ref "C31") (pin "1") (pinfunction "1_1") (pintype "passive"))
      (node (ref "C32") (pin "1") (pinfunction "1_1") (pintype "passive"))
      (node (ref "C33") (pin "1") (pinfunction "1_1") (pintype "passive"))
      (node (ref "C34") (pin "2") (pinfunction "2_2") (pintype "passive"))
      (node (ref "C35") (pin "2") (pinfunction "2_2") (pintype "passive"))
      (node (ref "C36") (pin "1") (pinfunction "1_1") (pintype "passive"))
      (node (ref "C37") (pin "1") (pinfunction "1_1") (pintype "passive"))
      (node (ref "C5") (pin "1") (pinfunction "1_1") (pintype "passive"))
      (node (ref "R5") (pin "1") (pinfunction "1_1") (pintype "passive"))
      (node (ref "U6") (pin "107") (pinfunction "VSS_107") (pintype "power_in"))
      (node (ref "U6") (pin "120") (pinfunction "VSS_120") (pintype "power_in"))
      (node (ref "U6") (pin "130") (pinfunction "VSS_130") (pintype "power_in"))
      (node (ref "U6") (pin "16") (pinfunction "VSS_16") (pintype "power_in"))
      (node (ref "U6") (pin "31") (pinfunction "VSSA_31") (pintype "power_in"))
      (node (ref "U6") (pin "38") (pinfunction "VSS_38") (pintype "power_in"))
      (node (ref "U6") (pin "51") (pinfunction "VSS_51") (pintype "power_in"))
      (node (ref "U6") (pin "61") (pinfunction "VSS_61") (pintype "power_in"))
      (node (ref "U6") (pin "83") (pinfunction "VSS_83") (pintype "power_in"))
      (node (ref "U6") (pin "94") (pinfunction "VSS_94") (pintype "power_in"))
    )
    (net (code "124") (name "Net-(U6B-BOOT0)") (class "Default")
      (node (ref "R5") (pin "2") (pinfunction "2_2") (pintype "passive"))
      (node (ref "U6") (pin "138") (pinfunction "BOOT0_138") (pintype "input"))
    )
    (net (code "125") (name "Net-(U6B-VCAP_1)") (class "Default")
      (node (ref "C37") (pin "2") (pinfunction "2_2") (pintype "passive"))
      (node (ref "U6") (pin "71") (pinfunction "VCAP_1_71") (pintype "power_in"))
    )
    (net (code "126") (name "Net-(U6B-VCAP_2)") (class "Default")
      (node (ref "C36") (pin "2") (pinfunction "2_2") (pintype "passive"))
      (node (ref "U6") (pin "106") (pinfunction "VCAP_2_106") (pintype "power_in"))
    )
    (net (code "127") (name "Net-(U6C-VBAT)") (class "Default")
      (node (ref "R20") (pin "2") (pinfunction "2_2") (pintype "passive"))
      (node (ref "U6") (pin "6") (pinfunction "VBAT_6") (pintype "power_in"))
    )
    (net (code "128") (name "Net-(U6C-VREF+)") (class "Default")
      (node (ref "C16") (pin "2") (pinfunction "2_2") (pintype "passive"))
      (node (ref "C17") (pin "2") (pinfunction "2_2") (pintype "passive"))
      (node (ref "R21") (pin "1") (pinfunction "1_1") (pintype "passive"))
      (node (ref "U6") (pin "32") (pinfunction "VREF+_32") (pintype "power_in"))
    )
    (net (code "129") (name "Net-(Y1-OSC1)") (class "Default")
      (node (ref "C34") (pin "1") (pinfunction "1_1") (pintype "passive"))
      (node (ref "R24") (pin "2") (pinfunction "2_2") (pintype "passive"))
      (node (ref "Y1") (pin "1") (pinfunction "OSC1_1") (pintype "passive"))
    )
    (net (code "130") (name "Net-(Y1-OSC2)") (class "Default")
      (node (ref "C35") (pin "1") (pinfunction "1_1") (pintype "passive"))
      (node (ref "R25") (pin "2") (pinfunction "2_2") (pintype "passive"))
      (node (ref "Y1") (pin "2") (pinfunction "OSC2_2") (pintype "passive"))
    )
    (net (code "131") (name "VDDA") (class "Default")
      (node (ref "C32") (pin "2") (pinfunction "2_2") (pintype "passive"))
      (node (ref "C33") (pin "2") (pinfunction "2_2") (pintype "passive"))
      (node (ref "L3") (pin "2") (pinfunction "2_2") (pintype "passive"))
      (node (ref "R21") (pin "2") (pinfunction "2_2") (pintype "passive"))
      (node (ref "R23") (pin "2") (pinfunction "2_2") (pintype "passive"))
      (node (ref "U6") (pin "33") (pinfunction "VDDA_33") (pintype "power_in"))
    )
  )
)
